# ESP_Controller.net
KiCad netlist of a schematic drawn in Altium Designer
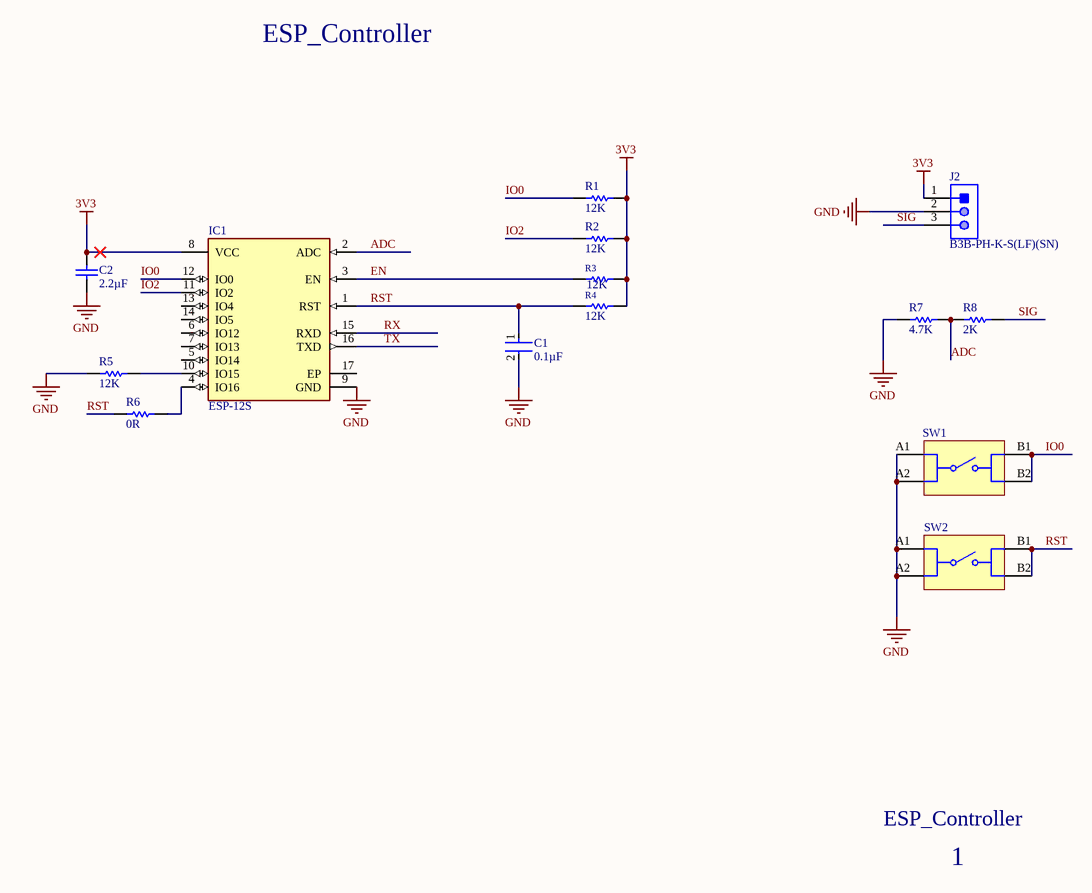
[diagram p0: ESP_Controller.SchDoc]

(export (version "E")
  (design (tool "Eeschema 10.0.6"))
  (components
    (comp (ref "C1")
      (value "0.1µF")
      (footprint "FP-CC0603-DA-MFG")
      (description "Capacitor Ceramic 0.1uF 6.3V X7R 10% 0603 Paper T/R")
      (libsource (lib "Altium Content Vault") (part "b4654b650e69147ec39a6b967a45e02"))
    )
    (comp (ref "C2")
      (value "2.2µF")
      (footprint "CAPC2013X145X50ML20T25")
      (fields (field (name "PART NUMBER") "C0805C225K9PACTU") (field (name "MANUFACTURER") "Kemet"))
      (libsource (lib "Altium Content Vault") (part "CAP"))
    )
    (comp (ref "IC1")
      (value "ESP-12S")
      (footprint "FP-ESP-12S-MFG")
      (description "RX TXRX MOD WIFI PCB TRACE SMD")
      (libsource (lib "Altium Content Vault") (part "0473e498d6bc78f349d0f2898a8422c"))
    )
    (comp (ref "J2")
      (value "B3B-PH-K-S(LF)(SN)")
      (footprint "JST-B3B-PH-K-S-3_V")
      (fields (field (name "MANUFACTURER") "JST"))
      (libsource (lib "Altium Content Vault") (part "CN-1P-M-R3"))
    )
    (comp (ref "R1")
      (value "12K")
      (footprint "RESC2013X70X40ML20T20")
      (fields (field (name "PART NUMBER") "ERJ-6GEYJ123V") (field (name "MANUFACTURER") "Panasonic"))
      (libsource (lib "Altium Content Vault") (part "RES"))
    )
    (comp (ref "R2")
      (value "12K")
      (footprint "RESC2013X70X40ML20T20")
      (fields (field (name "PART NUMBER") "ERJ-6GEYJ123V") (field (name "MANUFACTURER") "Panasonic"))
      (libsource (lib "Altium Content Vault") (part "RES"))
    )
    (comp (ref "R3")
      (value "12K")
      (footprint "RESC2013X70X40ML20T20")
      (fields (field (name "PART NUMBER") "ERJ-6GEYJ123V") (field (name "MANUFACTURER") "Panasonic"))
      (libsource (lib "Altium Content Vault") (part "RES"))
    )
    (comp (ref "R4")
      (value "12K")
      (footprint "RESC2013X70X40ML20T20")
      (fields (field (name "PART NUMBER") "ERJ-6GEYJ123V") (field (name "MANUFACTURER") "Panasonic"))
      (libsource (lib "Altium Content Vault") (part "RES"))
    )
    (comp (ref "R5")
      (value "12K")
      (footprint "RESC2013X70X40ML20T20")
      (fields (field (name "PART NUMBER") "ERJ-6GEYJ123V") (field (name "MANUFACTURER") "Panasonic"))
      (libsource (lib "Altium Content Vault") (part "RES"))
    )
    (comp (ref "R6")
      (value "0R")
      (footprint "RESC2013X70X40NL20T20")
      (description "Chip Resistor, 0 Ohm, +/- 1%, 0.125 W, -55 to 155 degC, 0805 (2012 Metric), RoHS, Tape and Reel")
      (fields (field (name "PARTNUMBER") "ERJ-6GEY0R00V") (field (name "TOLERANCE") "5%"))
      (libsource (lib "Altium Content Vault") (part "RES-2"))
    )
    (comp (ref "R7")
      (value "4.7K")
      (footprint "RESC2013X60X40ML20T25")
      (fields (field (name "PART NUMBER") "ERA6AEB472V") (field (name "MANUFACTURER") "Panasonic"))
      (libsource (lib "Altium Content Vault") (part "RES"))
    )
    (comp (ref "R8")
      (value "2K")
      (footprint "RESC2013X60X40ML20T25")
      (fields (field (name "PART NUMBER") "ERA6AEB202V") (field (name "MANUFACTURER") "Panasonic"))
      (libsource (lib "Altium Content Vault") (part "RES"))
    )
    (comp (ref "SW1")
      (value "430773051825")
      (footprint "430773051825")
      (description "Tactile Switch, 0.05A, 12Vdc, 250Gf, Smd Rohs Compliant: Yes")
      (libsource (lib "Altium Content Vault") (part "SPST-NO_4P"))
    )
    (comp (ref "SW2")
      (value "430773051825")
      (footprint "430773051825")
      (description "Tactile Switch, 0.05A, 12Vdc, 250Gf, Smd Rohs Compliant: Yes")
      (libsource (lib "Altium Content Vault") (part "SPST-NO_4P"))
    )
  )
  (nets
    (net (code "1") (name "/ADC") (class "Default")
      (node (ref "IC1") (pin "2") (pinfunction "ADC_2") (pintype "input"))
      (node (ref "R7") (pin "2") (pinfunction "2_2") (pintype "passive"))
      (node (ref "R8") (pin "1") (pinfunction "1_1") (pintype "passive"))
    )
    (net (code "2") (name "/EN") (class "Default")
      (node (ref "IC1") (pin "3") (pinfunction "EN_3") (pintype "input"))
      (node (ref "R3") (pin "1") (pinfunction "1_1") (pintype "passive"))
    )
    (net (code "3") (name "/IO0") (class "Default")
      (node (ref "IC1") (pin "12") (pinfunction "IO0_12") (pintype "bidirectional"))
      (node (ref "R1") (pin "1") (pinfunction "1_1") (pintype "passive"))
      (node (ref "SW1") (pin "B1") (pinfunction "B1_B1") (pintype "passive"))
      (node (ref "SW1") (pin "B2") (pinfunction "B2_B2") (pintype "passive"))
    )
    (net (code "4") (name "/IO2") (class "Default")
      (node (ref "IC1") (pin "11") (pinfunction "IO2_11") (pintype "bidirectional"))
      (node (ref "R2") (pin "1") (pinfunction "1_1") (pintype "passive"))
    )
    (net (code "5") (name "/RST") (class "Default")
      (node (ref "C1") (pin "1") (pinfunction "1_1") (pintype "passive"))
      (node (ref "IC1") (pin "1") (pinfunction "RST_1") (pintype "input"))
      (node (ref "R4") (pin "1") (pinfunction "1_1") (pintype "passive"))
      (node (ref "R6") (pin "1") (pinfunction "1_1") (pintype "passive"))
      (node (ref "SW2") (pin "B1") (pinfunction "B1_B1") (pintype "passive"))
      (node (ref "SW2") (pin "B2") (pinfunction "B2_B2") (pintype "passive"))
    )
    (net (code "6") (name "/RX") (class "Default")
      (node (ref "IC1") (pin "15") (pinfunction "RXD_15") (pintype "input"))
    )
    (net (code "7") (name "/SIG") (class "Default")
      (node (ref "J2") (pin "3") (pinfunction "3_3") (pintype "passive"))
      (node (ref "R8") (pin "2") (pinfunction "2_2") (pintype "passive"))
    )
    (net (code "8") (name "/TX") (class "Default")
      (node (ref "IC1") (pin "16") (pinfunction "TXD_16") (pintype "output"))
    )
    (net (code "9") (name "3V3") (class "Default")
      (node (ref "C2") (pin "2") (pinfunction "2_2") (pintype "passive"))
      (node (ref "IC1") (pin "8") (pinfunction "VCC_8") (pintype "power_in"))
      (node (ref "J2") (pin "1") (pinfunction "1_1") (pintype "passive"))
      (node (ref "R1") (pin "2") (pinfunction "2_2") (pintype "passive"))
      (node (ref "R2") (pin "2") (pinfunction "2_2") (pintype "passive"))
      (node (ref "R3") (pin "2") (pinfunction "2_2") (pintype "passive"))
      (node (ref "R4") (pin "2") (pinfunction "2_2") (pintype "passive"))
    )
    (net (code "10") (name "GND") (class "Default")
      (node (ref "C1") (pin "2") (pinfunction "2_2") (pintype "passive"))
      (node (ref "C2") (pin "1") (pinfunction "1_1") (pintype "passive"))
      (node (ref "IC1") (pin "9") (pinfunction "GND_9") (pintype "power_in"))
      (node (ref "J2") (pin "2") (pinfunction "2_2") (pintype "passive"))
      (node (ref "R5") (pin "1") (pinfunction "1_1") (pintype "passive"))
      (node (ref "R7") (pin "1") (pinfunction "1_1") (pintype "passive"))
      (node (ref "SW1") (pin "A1") (pinfunction "A1_A1") (pintype "passive"))
      (node (ref "SW1") (pin "A2") (pinfunction "A2_A2") (pintype "passive"))
      (node (ref "SW2") (pin "A1") (pinfunction "A1_A1") (pintype "passive"))
      (node (ref "SW2") (pin "A2") (pinfunction "A2_A2") (pintype "passive"))
    )
    (net (code "11") (name "Net-(IC1-IO15)") (class "Default")
      (node (ref "IC1") (pin "10") (pinfunction "IO15_10") (pintype "bidirectional"))
      (node (ref "R5") (pin "2") (pinfunction "2_2") (pintype "passive"))
    )
    (net (code "12") (name "Net-(IC1-IO16)") (class "Default")
      (node (ref "IC1") (pin "4") (pinfunction "IO16_4") (pintype "bidirectional"))
      (node (ref "R6") (pin "2") (pinfunction "2_2") (pintype "passive"))
    )
    (net (code "13") (name "unconnected-(IC1-EP-Pad17)") (class "Default")
      (node (ref "IC1") (pin "17") (pinfunction "EP_17") (pintype "power_in"))
    )
    (net (code "14") (name "unconnected-(IC1-IO4-Pad13)") (class "Default")
      (node (ref "IC1") (pin "13") (pinfunction "IO4_13") (pintype "bidirectional"))
    )
    (net (code "15") (name "unconnected-(IC1-IO5-Pad14)") (class "Default")
      (node (ref "IC1") (pin "14") (pinfunction "IO5_14") (pintype "bidirectional"))
    )
    (net (code "16") (name "unconnected-(IC1-IO12-Pad6)") (class "Default")
      (node (ref "IC1") (pin "6") (pinfunction "IO12_6") (pintype "bidirectional"))
    )
    (net (code "17") (name "unconnected-(IC1-IO13-Pad7)") (class "Default")
      (node (ref "IC1") (pin "7") (pinfunction "IO13_7") (pintype "bidirectional"))
    )
    (net (code "18") (name "unconnected-(IC1-IO14-Pad5)") (class "Default")
      (node (ref "IC1") (pin "5") (pinfunction "IO14_5") (pintype "bidirectional"))
    )
  )
)
